# LeCoolStick-v1_1.net
KiCad netlist of a schematic drawn in EAGLE
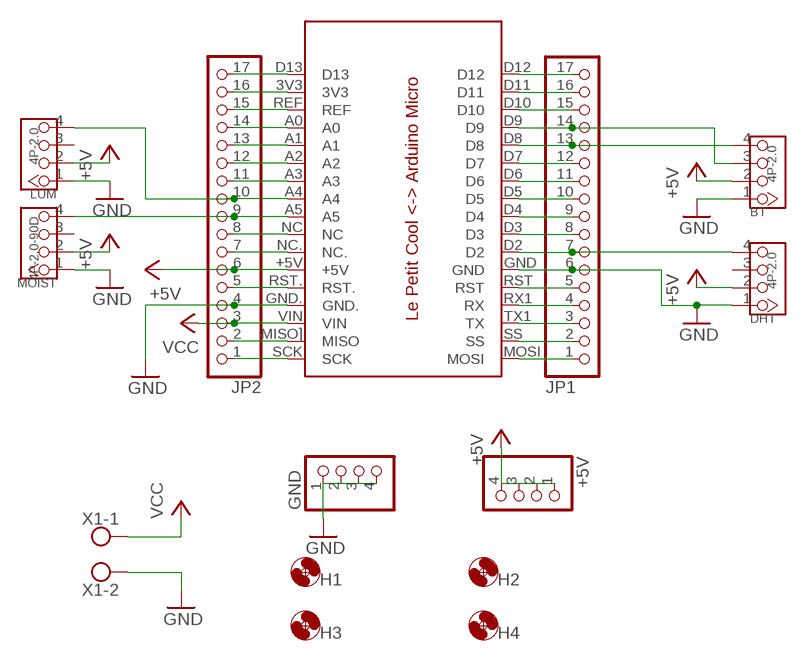
[diagram p0: schematic, sheet 1]

(export (version "E")
  (design (tool "Eeschema 10.0.6"))
  (components
    (comp (ref "+5V")
      (value "PINHD-1X4")
      (footprint "eagle-import:1X04")
      (libsource (lib "eagle-import") (part "PINHD-1X4"))
    )
    (comp (ref "BT")
      (value "4P-2.0")
      (footprint "eagle-import:4P-2.0")
      (libsource (lib "eagle-import") (part "TWIG-4P-2.0-2.0"))
    )
    (comp (ref "DHT")
      (value "4P-2.0")
      (footprint "eagle-import:4P-2.0")
      (libsource (lib "eagle-import") (part "TWIG-4P-2.0-2.0"))
    )
    (comp (ref "GND")
      (value "PINHD-1X4")
      (footprint "eagle-import:1X04")
      (libsource (lib "eagle-import") (part "PINHD-1X4"))
    )
    (comp (ref "H1")
      (value "MOUNT-HOLEHOLE-2.8")
      (footprint "eagle-import:HOLE-2,8")
      (libsource (lib "eagle-import") (part "MOUNT-HOLEHOLE-2.8"))
    )
    (comp (ref "H2")
      (value "MOUNT-HOLEHOLE-2.8")
      (footprint "eagle-import:HOLE-2,8")
      (libsource (lib "eagle-import") (part "MOUNT-HOLEHOLE-2.8"))
    )
    (comp (ref "H3")
      (value "MOUNT-HOLEHOLE-2.8")
      (footprint "eagle-import:HOLE-2,8")
      (libsource (lib "eagle-import") (part "MOUNT-HOLEHOLE-2.8"))
    )
    (comp (ref "H4")
      (value "MOUNT-HOLEHOLE-2.8")
      (footprint "eagle-import:HOLE-2,8")
      (libsource (lib "eagle-import") (part "MOUNT-HOLEHOLE-2.8"))
    )
    (comp (ref "JP1")
      (value "PINHD-1X17")
      (footprint "eagle-import:1X17")
      (libsource (lib "eagle-import") (part "PINHD-1X17"))
    )
    (comp (ref "JP2")
      (value "PINHD-1X17")
      (footprint "eagle-import:1X17")
      (libsource (lib "eagle-import") (part "PINHD-1X17"))
    )
    (comp (ref "LUM")
      (value "4P-2.0")
      (footprint "eagle-import:4P-2.0")
      (libsource (lib "eagle-import") (part "TWIG-4P-2.0-2.0"))
    )
    (comp (ref "MOIST")
      (value "4P-2.0-90D")
      (footprint "eagle-import:4P-2.0-90D")
      (libsource (lib "eagle-import") (part "TWIG-4P-2.0'90D'"))
    )
    (comp (ref "PCB1")
      (value "SHIELD_MICRO")
      (footprint "eagle-import:SHIELD_MICRO")
      (libsource (lib "eagle-import") (part "SHIELD_MICRO"))
    )
    (comp (ref "X1")
      (value "AK500/2")
      (footprint "eagle-import:AK500_2")
      (libsource (lib "eagle-import") (part "AK500/2"))
    )
  )
  (nets
    (net (code "1") (name "+5V") (class "Default")
      (node (ref "+5V") (pin "1") (pinfunction "1_1") (pintype "passive"))
      (node (ref "+5V") (pin "2") (pinfunction "2_2") (pintype "passive"))
      (node (ref "+5V") (pin "3") (pinfunction "3_3") (pintype "passive"))
      (node (ref "+5V") (pin "4") (pinfunction "4_4") (pintype "passive"))
      (node (ref "BT") (pin "2") (pinfunction "2_2") (pintype "bidirectional"))
      (node (ref "DHT") (pin "2") (pinfunction "2_2") (pintype "bidirectional"))
      (node (ref "JP2") (pin "6") (pinfunction "6_6") (pintype "passive"))
      (node (ref "LUM") (pin "2") (pinfunction "2_2") (pintype "bidirectional"))
      (node (ref "MOIST") (pin "2") (pinfunction "2_2") (pintype "bidirectional"))
      (node (ref "PCB1") (pin "+5V") (pinfunction "+5V_+5V") (pintype "bidirectional"))
    )
    (net (code "2") (name "GND") (class "Default")
      (node (ref "BT") (pin "1") (pinfunction "1_1") (pintype "bidirectional"))
      (node (ref "DHT") (pin "1") (pinfunction "1_1") (pintype "bidirectional"))
      (node (ref "GND") (pin "1") (pinfunction "1_1") (pintype "passive"))
      (node (ref "GND") (pin "2") (pinfunction "2_2") (pintype "passive"))
      (node (ref "GND") (pin "3") (pinfunction "3_3") (pintype "passive"))
      (node (ref "GND") (pin "4") (pinfunction "4_4") (pintype "passive"))
      (node (ref "JP1") (pin "6") (pinfunction "6_6") (pintype "passive"))
      (node (ref "JP2") (pin "4") (pinfunction "4_4") (pintype "passive"))
      (node (ref "LUM") (pin "1") (pinfunction "1_1") (pintype "bidirectional"))
      (node (ref "MOIST") (pin "1") (pinfunction "1_1") (pintype "bidirectional"))
      (node (ref "PCB1") (pin "GND") (pinfunction "GND_GND") (pintype "bidirectional"))
      (node (ref "PCB1") (pin "GND.") (pinfunction "GND._GND.") (pintype "bidirectional"))
      (node (ref "X1") (pin "2") (pinfunction "KL_2") (pintype "passive"))
    )
    (net (code "3") (name "Net-(BT-Pad3)") (class "Default")
      (node (ref "BT") (pin "3") (pinfunction "3_3") (pintype "bidirectional"))
      (node (ref "JP1") (pin "14") (pinfunction "14_14") (pintype "passive"))
      (node (ref "PCB1") (pin "D9") (pinfunction "D9_D9") (pintype "bidirectional"))
    )
    (net (code "4") (name "Net-(BT-Pad4)") (class "Default")
      (node (ref "BT") (pin "4") (pinfunction "4_4") (pintype "bidirectional"))
      (node (ref "JP1") (pin "13") (pinfunction "13_13") (pintype "passive"))
      (node (ref "PCB1") (pin "D8") (pinfunction "D8_D8") (pintype "bidirectional"))
    )
    (net (code "5") (name "Net-(DHT-Pad4)") (class "Default")
      (node (ref "DHT") (pin "4") (pinfunction "4_4") (pintype "bidirectional"))
      (node (ref "JP1") (pin "7") (pinfunction "7_7") (pintype "passive"))
      (node (ref "PCB1") (pin "D2") (pinfunction "D2_D2") (pintype "bidirectional"))
    )
    (net (code "6") (name "Net-(JP1-Pad1)") (class "Default")
      (node (ref "JP1") (pin "1") (pinfunction "1_1") (pintype "passive"))
      (node (ref "PCB1") (pin "MOSI") (pinfunction "MOSI_MOSI") (pintype "bidirectional"))
    )
    (net (code "7") (name "Net-(JP1-Pad2)") (class "Default")
      (node (ref "JP1") (pin "2") (pinfunction "2_2") (pintype "passive"))
      (node (ref "PCB1") (pin "SS") (pinfunction "SS_SS") (pintype "bidirectional"))
    )
    (net (code "8") (name "Net-(JP1-Pad5)") (class "Default")
      (node (ref "JP1") (pin "5") (pinfunction "5_5") (pintype "passive"))
      (node (ref "PCB1") (pin "RST") (pinfunction "RST_RST") (pintype "bidirectional"))
    )
    (net (code "9") (name "Net-(JP1-Pad8)") (class "Default")
      (node (ref "JP1") (pin "8") (pinfunction "8_8") (pintype "passive"))
      (node (ref "PCB1") (pin "D3") (pinfunction "D3_D3") (pintype "bidirectional"))
    )
    (net (code "10") (name "Net-(JP1-Pad9)") (class "Default")
      (node (ref "JP1") (pin "9") (pinfunction "9_9") (pintype "passive"))
      (node (ref "PCB1") (pin "D4") (pinfunction "D4_D4") (pintype "bidirectional"))
    )
    (net (code "11") (name "Net-(JP1-Pad10)") (class "Default")
      (node (ref "JP1") (pin "10") (pinfunction "10_10") (pintype "passive"))
      (node (ref "PCB1") (pin "D5") (pinfunction "D5_D5") (pintype "bidirectional"))
    )
    (net (code "12") (name "Net-(JP1-Pad11)") (class "Default")
      (node (ref "JP1") (pin "11") (pinfunction "11_11") (pintype "passive"))
      (node (ref "PCB1") (pin "D6") (pinfunction "D6_D6") (pintype "bidirectional"))
    )
    (net (code "13") (name "Net-(JP1-Pad12)") (class "Default")
      (node (ref "JP1") (pin "12") (pinfunction "12_12") (pintype "passive"))
      (node (ref "PCB1") (pin "D7") (pinfunction "D7_D7") (pintype "bidirectional"))
    )
    (net (code "14") (name "Net-(JP1-Pad15)") (class "Default")
      (node (ref "JP1") (pin "15") (pinfunction "15_15") (pintype "passive"))
      (node (ref "PCB1") (pin "D10") (pinfunction "D10_D10") (pintype "bidirectional"))
    )
    (net (code "15") (name "Net-(JP1-Pad16)") (class "Default")
      (node (ref "JP1") (pin "16") (pinfunction "16_16") (pintype "passive"))
      (node (ref "PCB1") (pin "D11") (pinfunction "D11_D11") (pintype "bidirectional"))
    )
    (net (code "16") (name "Net-(JP1-Pad17)") (class "Default")
      (node (ref "JP1") (pin "17") (pinfunction "17_17") (pintype "passive"))
      (node (ref "PCB1") (pin "D12") (pinfunction "D12_D12") (pintype "bidirectional"))
    )
    (net (code "17") (name "Net-(JP2-Pad1)") (class "Default")
      (node (ref "JP2") (pin "1") (pinfunction "1_1") (pintype "passive"))
      (node (ref "PCB1") (pin "SCK") (pinfunction "SCK_SCK") (pintype "bidirectional"))
    )
    (net (code "18") (name "Net-(JP2-Pad5)") (class "Default")
      (node (ref "JP2") (pin "5") (pinfunction "5_5") (pintype "passive"))
      (node (ref "PCB1") (pin "RST.") (pinfunction "RST._RST.") (pintype "bidirectional"))
    )
    (net (code "19") (name "Net-(JP2-Pad7)") (class "Default")
      (node (ref "JP2") (pin "7") (pinfunction "7_7") (pintype "passive"))
      (node (ref "PCB1") (pin "NC.") (pinfunction "NC._NC.") (pintype "bidirectional"))
    )
    (net (code "20") (name "Net-(JP2-Pad8)") (class "Default")
      (node (ref "JP2") (pin "8") (pinfunction "8_8") (pintype "passive"))
      (node (ref "PCB1") (pin "NC") (pinfunction "NC_NC") (pintype "bidirectional"))
    )
    (net (code "21") (name "Net-(JP2-Pad9)") (class "Default")
      (node (ref "JP2") (pin "9") (pinfunction "9_9") (pintype "passive"))
      (node (ref "MOIST") (pin "4") (pinfunction "4_4") (pintype "bidirectional"))
      (node (ref "PCB1") (pin "A5") (pinfunction "A5_A5") (pintype "bidirectional"))
    )
    (net (code "22") (name "Net-(JP2-Pad10)") (class "Default")
      (node (ref "JP2") (pin "10") (pinfunction "10_10") (pintype "passive"))
      (node (ref "LUM") (pin "4") (pinfunction "4_4") (pintype "bidirectional"))
      (node (ref "PCB1") (pin "A4") (pinfunction "A4_A4") (pintype "bidirectional"))
    )
    (net (code "23") (name "Net-(JP2-Pad11)") (class "Default")
      (node (ref "JP2") (pin "11") (pinfunction "11_11") (pintype "passive"))
      (node (ref "PCB1") (pin "A3") (pinfunction "A3_A3") (pintype "bidirectional"))
    )
    (net (code "24") (name "Net-(JP2-Pad12)") (class "Default")
      (node (ref "JP2") (pin "12") (pinfunction "12_12") (pintype "passive"))
      (node (ref "PCB1") (pin "A2") (pinfunction "A2_A2") (pintype "bidirectional"))
    )
    (net (code "25") (name "Net-(JP2-Pad13)") (class "Default")
      (node (ref "JP2") (pin "13") (pinfunction "13_13") (pintype "passive"))
      (node (ref "PCB1") (pin "A1") (pinfunction "A1_A1") (pintype "bidirectional"))
    )
    (net (code "26") (name "Net-(JP2-Pad14)") (class "Default")
      (node (ref "JP2") (pin "14") (pinfunction "14_14") (pintype "passive"))
      (node (ref "PCB1") (pin "A0") (pinfunction "A0_A0") (pintype "bidirectional"))
    )
    (net (code "27") (name "Net-(JP2-Pad15)") (class "Default")
      (node (ref "JP2") (pin "15") (pinfunction "15_15") (pintype "passive"))
      (node (ref "PCB1") (pin "REF") (pinfunction "REF_REF") (pintype "bidirectional"))
    )
    (net (code "28") (name "Net-(JP2-Pad16)") (class "Default")
      (node (ref "JP2") (pin "16") (pinfunction "16_16") (pintype "passive"))
      (node (ref "PCB1") (pin "3V3") (pinfunction "3V3_3V3") (pintype "bidirectional"))
    )
    (net (code "29") (name "Net-(JP2-Pad17)") (class "Default")
      (node (ref "JP2") (pin "17") (pinfunction "17_17") (pintype "passive"))
      (node (ref "PCB1") (pin "D13") (pinfunction "D13_D13") (pintype "bidirectional"))
    )
    (net (code "30") (name "Net-(PCB1-MISO)") (class "Default")
      (node (ref "JP2") (pin "2") (pinfunction "2_2") (pintype "passive"))
      (node (ref "PCB1") (pin "MISO]") (pinfunction "MISO_MISO]") (pintype "bidirectional"))
    )
    (net (code "31") (name "Net-(PCB1-RX)") (class "Default")
      (node (ref "JP1") (pin "4") (pinfunction "4_4") (pintype "passive"))
      (node (ref "PCB1") (pin "RX1") (pinfunction "RX_RX1") (pintype "bidirectional"))
    )
    (net (code "32") (name "Net-(PCB1-TX)") (class "Default")
      (node (ref "JP1") (pin "3") (pinfunction "3_3") (pintype "passive"))
      (node (ref "PCB1") (pin "TX1") (pinfunction "TX_TX1") (pintype "bidirectional"))
    )
    (net (code "33") (name "VCC") (class "Default")
      (node (ref "JP2") (pin "3") (pinfunction "3_3") (pintype "passive"))
      (node (ref "PCB1") (pin "VIN") (pinfunction "VIN_VIN") (pintype "bidirectional"))
      (node (ref "X1") (pin "1") (pinfunction "KL_1") (pintype "passive"))
    )
    (net (code "34") (name "unconnected-(DHT-Pad3)") (class "Default")
      (node (ref "DHT") (pin "3") (pinfunction "3_3") (pintype "bidirectional"))
    )
    (net (code "35") (name "unconnected-(LUM-Pad3)") (class "Default")
      (node (ref "LUM") (pin "3") (pinfunction "3_3") (pintype "bidirectional"))
    )
    (net (code "36") (name "unconnected-(MOIST-Pad3)") (class "Default")
      (node (ref "MOIST") (pin "3") (pinfunction "3_3") (pintype "bidirectional"))
    )
  )
)
